# Schematic.net
KiCad netlist of a schematic drawn in EasyEDA
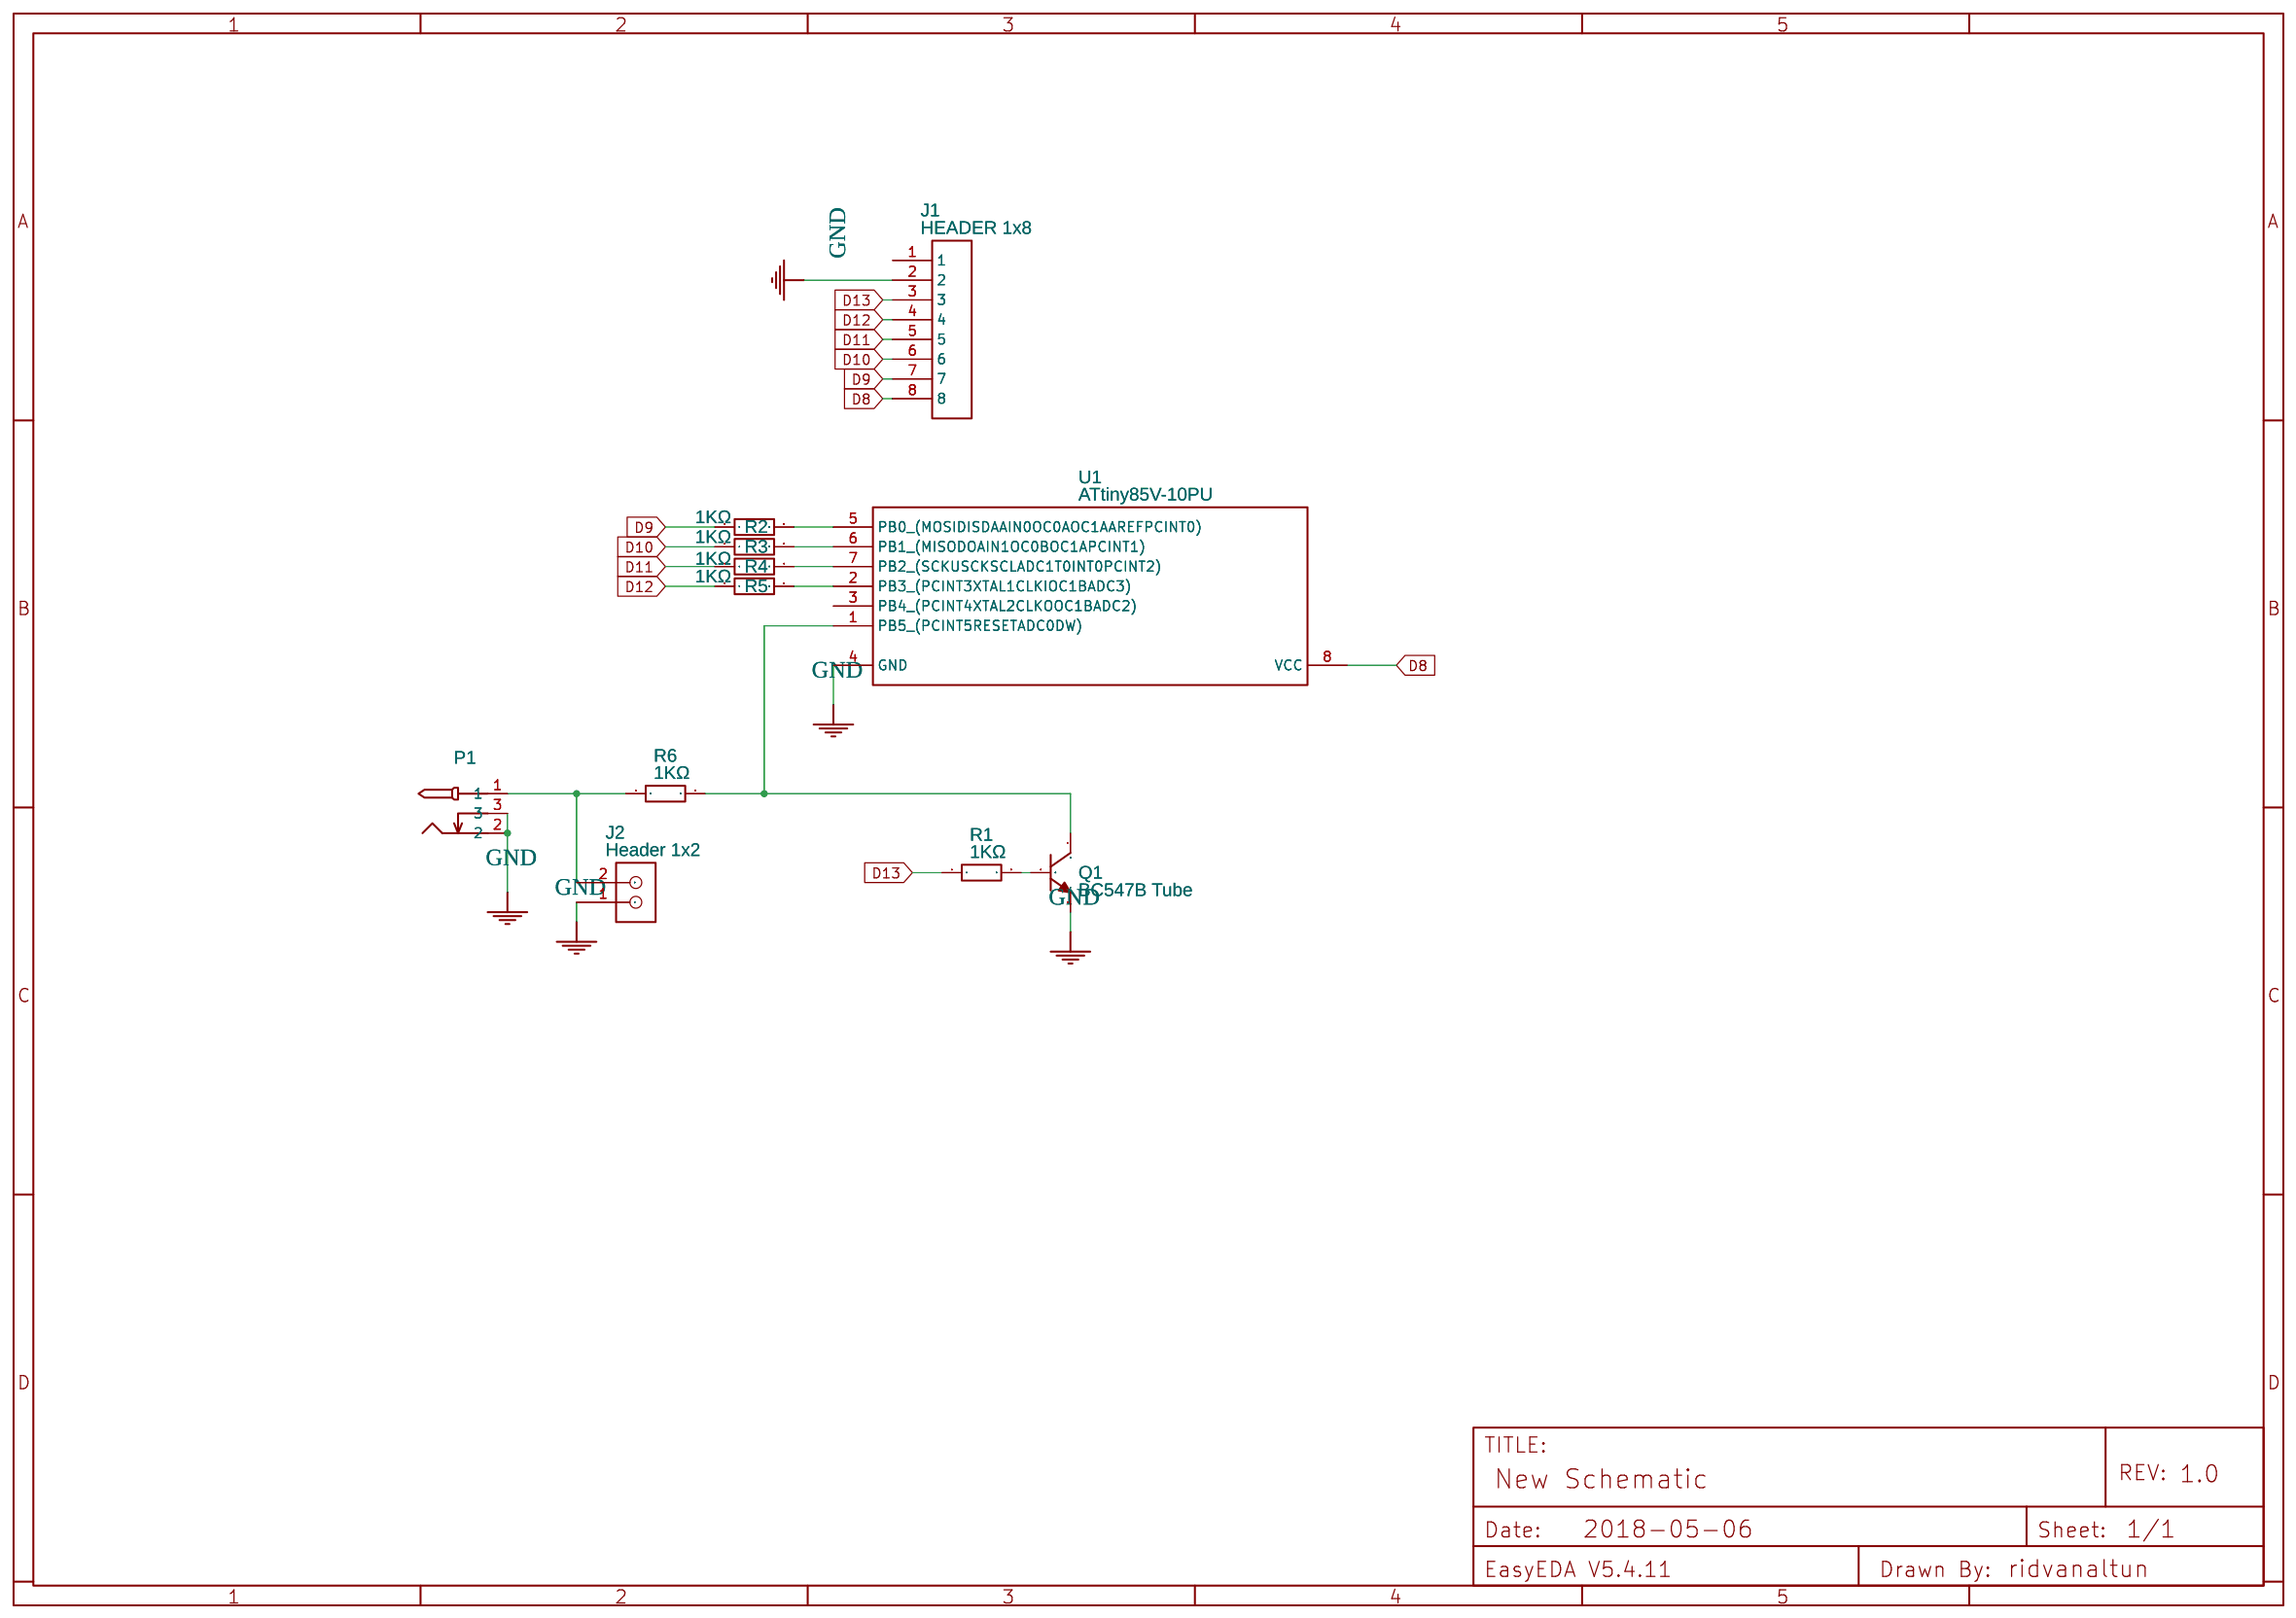
[diagram p0: schematic sheet]

(export (version "E")
  (design (tool "Eeschema 10.0.6"))
  (components
    (comp (ref "J1")
      (value "HEADER 1x8")
      (fields (field (name "BOM_Manufacturer Part") "?"))
      (libsource (lib "") (part "Unknown_465_115"))
    )
    (comp (ref "J2")
      (value "Header 1x2")
      (fields (field (name "BOM_Manufacturer Part") "?"))
      (libsource (lib "") (part "Unknown_315_420"))
    )
    (comp (ref "P1") (value "DC-005 5.5-2.0MM") (libsource (lib "") (part "Unknown_230_405")))
    (comp (ref "Q1") (value "BC547B Tube") (libsource (lib "") (part "Unknown_535_435")))
    (comp (ref "R1")
      (value "1KΩ")
      (fields (field (name "BOM_Manufacturer Part") "CFR0S2J0102A10"))
      (libsource (lib "") (part "CFR0S2J0102A10"))
    )
    (comp (ref "R2")
      (value "1KΩ")
      (fields (field (name "BOM_Manufacturer Part") "CFR0S2J0102A10"))
      (libsource (lib "") (part "CFR0S2J0102A10"))
    )
    (comp (ref "R3")
      (value "1KΩ")
      (fields (field (name "BOM_Manufacturer Part") "CFR0S2J0102A10"))
      (libsource (lib "") (part "CFR0S2J0102A10"))
    )
    (comp (ref "R4")
      (value "1KΩ")
      (fields (field (name "BOM_Manufacturer Part") "CFR0S2J0102A10"))
      (libsource (lib "") (part "CFR0S2J0102A10"))
    )
    (comp (ref "R5")
      (value "1KΩ")
      (fields (field (name "BOM_Manufacturer Part") "CFR0S2J0102A10"))
      (libsource (lib "") (part "CFR0S2J0102A10"))
    )
    (comp (ref "R6")
      (value "1KΩ")
      (fields (field (name "BOM_Manufacturer Part") "CFR0S2J0102A10"))
      (libsource (lib "") (part "CFR0S2J0102A10"))
    )
    (comp (ref "U1")
      (value "ATtiny85V-10PU")
      (fields (field (name "BOM_Manufacturer Part") "?"))
      (libsource (lib "") (part "Unknown_545_300"))
    )
  )
  (nets
    (net (code "1") (name "D8") (class "Default")
      (node (ref "J1") (pin "8") (pinfunction "8_8") (pintype "unspecified"))
      (node (ref "U1") (pin "8") (pinfunction "VCC_8") (pintype "passive"))
    )
    (net (code "2") (name "D9") (class "Default")
      (node (ref "J1") (pin "7") (pinfunction "7_7") (pintype "unspecified"))
      (node (ref "R2") (pin "1") (pinfunction "1_1") (pintype "input"))
    )
    (net (code "3") (name "D10") (class "Default")
      (node (ref "J1") (pin "6") (pinfunction "6_6") (pintype "unspecified"))
      (node (ref "R3") (pin "1") (pinfunction "1_1") (pintype "input"))
    )
    (net (code "4") (name "D11") (class "Default")
      (node (ref "J1") (pin "5") (pinfunction "5_5") (pintype "unspecified"))
      (node (ref "R4") (pin "1") (pinfunction "1_1") (pintype "input"))
    )
    (net (code "5") (name "D12") (class "Default")
      (node (ref "J1") (pin "4") (pinfunction "4_4") (pintype "unspecified"))
      (node (ref "R5") (pin "1") (pinfunction "1_1") (pintype "input"))
    )
    (net (code "6") (name "D13") (class "Default")
      (node (ref "J1") (pin "3") (pinfunction "3_3") (pintype "unspecified"))
      (node (ref "R1") (pin "1") (pinfunction "1_1") (pintype "input"))
    )
    (net (code "7") (name "GND") (class "Default")
      (node (ref "J1") (pin "2") (pinfunction "2_2") (pintype "unspecified"))
      (node (ref "J2") (pin "1") (pinfunction "1_1") (pintype "bidirectional"))
      (node (ref "P1") (pin "2") (pinfunction "2_2") (pintype "unspecified"))
      (node (ref "P1") (pin "3") (pinfunction "3_3") (pintype "unspecified"))
      (node (ref "Q1") (pin "3") (pinfunction "E_3") (pintype "unspecified"))
      (node (ref "U1") (pin "4") (pinfunction "GND_4") (pintype "passive"))
    )
    (net (code "8") (name "Net-(J2-Pad2)") (class "Default")
      (node (ref "J2") (pin "2") (pinfunction "2_2") (pintype "bidirectional"))
      (node (ref "P1") (pin "1") (pinfunction "1_1") (pintype "unspecified"))
      (node (ref "R6") (pin "1") (pinfunction "1_1") (pintype "input"))
    )
    (net (code "9") (name "Net-(Q1-B)") (class "Default")
      (node (ref "Q1") (pin "2") (pinfunction "B_2") (pintype "unspecified"))
      (node (ref "R1") (pin "2") (pinfunction "2_2") (pintype "input"))
    )
    (net (code "10") (name "Net-(Q1-C)") (class "Default")
      (node (ref "Q1") (pin "1") (pinfunction "C_1") (pintype "unspecified"))
      (node (ref "R6") (pin "2") (pinfunction "2_2") (pintype "input"))
      (node (ref "U1") (pin "1") (pinfunction "PB5_(PCINT5RESETADC0DW)_1") (pintype "bidirectional"))
    )
    (net (code "11") (name "Net-(U1-PB0_(MOSIDISDAAIN0OC0AOC1AAREFPCINT0))") (class "Default")
      (node (ref "R2") (pin "2") (pinfunction "2_2") (pintype "input"))
      (node (ref "U1") (pin "5") (pinfunction "PB0_(MOSIDISDAAIN0OC0AOC1AAREFPCINT0)_5") (pintype "bidirectional"))
    )
    (net (code "12") (name "Net-(U1-PB1_(MISODOAIN1OC0BOC1APCINT1))") (class "Default")
      (node (ref "R3") (pin "2") (pinfunction "2_2") (pintype "input"))
      (node (ref "U1") (pin "6") (pinfunction "PB1_(MISODOAIN1OC0BOC1APCINT1)_6") (pintype "bidirectional"))
    )
    (net (code "13") (name "Net-(U1-PB2_(SCKUSCKSCLADC1T0INT0PCINT2))") (class "Default")
      (node (ref "R4") (pin "2") (pinfunction "2_2") (pintype "input"))
      (node (ref "U1") (pin "7") (pinfunction "PB2_(SCKUSCKSCLADC1T0INT0PCINT2)_7") (pintype "bidirectional"))
    )
    (net (code "14") (name "Net-(U1-PB3_(PCINT3XTAL1CLKIOC1BADC3))") (class "Default")
      (node (ref "R5") (pin "2") (pinfunction "2_2") (pintype "input"))
      (node (ref "U1") (pin "2") (pinfunction "PB3_(PCINT3XTAL1CLKIOC1BADC3)_2") (pintype "bidirectional"))
    )
    (net (code "15") (name "unconnected-(J1-Pad1)") (class "Default")
      (node (ref "J1") (pin "1") (pinfunction "1_1") (pintype "unspecified"))
    )
    (net (code "16") (name "unconnected-(U1-PB4_(PCINT4XTAL2CLKOOC1BADC2)-Pad3)") (class "Default")
      (node (ref "U1") (pin "3") (pinfunction "PB4_(PCINT4XTAL2CLKOOC1BADC2)_3") (pintype "bidirectional"))
    )
  )
)
